# Current_Controller.net
KiCad netlist of a schematic drawn in EAGLE
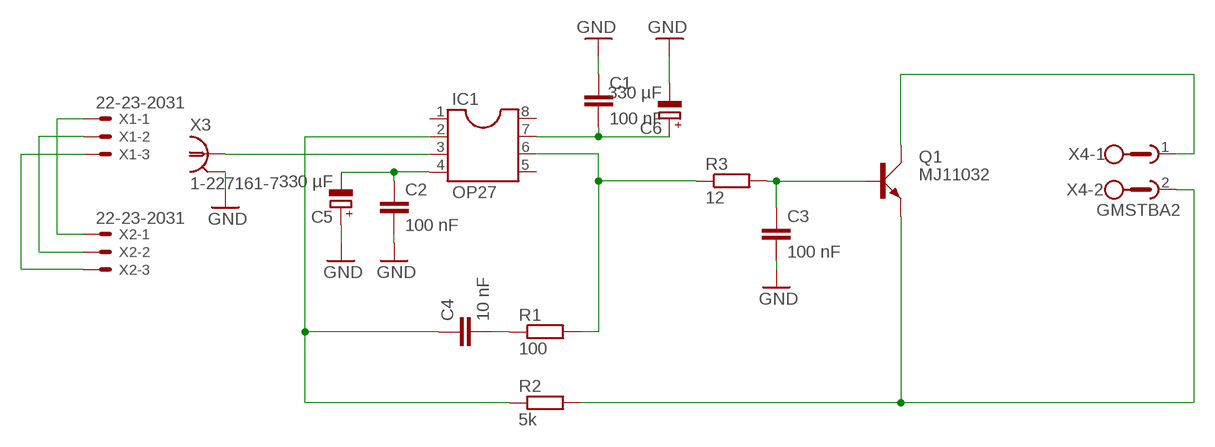
[diagram p0: schematic, sheet 1]

(export (version "E")
  (design (tool "Eeschema 10.0.6"))
  (components
    (comp (ref "C1")
      (value "100 nF")
      (footprint "eagle-import:C025-050X050")
      (libsource (lib "eagle-import") (part "C-EU025-050X050"))
    )
    (comp (ref "C2")
      (value "100 nF")
      (footprint "eagle-import:C025-050X050")
      (libsource (lib "eagle-import") (part "C-EU025-050X050"))
    )
    (comp (ref "C3")
      (value "100 nF")
      (footprint "eagle-import:C025-050X050")
      (libsource (lib "eagle-import") (part "C-EU025-050X050"))
    )
    (comp (ref "C4")
      (value "10 nF")
      (footprint "eagle-import:C025-050X050")
      (libsource (lib "eagle-import") (part "C-EU025-050X050"))
    )
    (comp (ref "C5")
      (value "330 µF")
      (footprint "eagle-import:E5-8,5")
      (libsource (lib "eagle-import") (part "CPOL-EUE5-8.5"))
    )
    (comp (ref "C6")
      (value "330 µF")
      (footprint "eagle-import:E5-8,5")
      (libsource (lib "eagle-import") (part "CPOL-EUE5-8.5"))
    )
    (comp (ref "IC1")
      (value "OP27")
      (footprint "eagle-import:DIL08")
      (libsource (lib "eagle-import") (part "DIL8"))
    )
    (comp (ref "Q1")
      (value "MJ11032")
      (footprint "eagle-import:TO3A")
      (libsource (lib "eagle-import") (part "2N3055"))
    )
    (comp (ref "R1")
      (value "100")
      (footprint "eagle-import:0309_12")
      (libsource (lib "eagle-import") (part "R-EU_0309/12"))
    )
    (comp (ref "R2")
      (value "5k")
      (footprint "eagle-import:0309_12")
      (libsource (lib "eagle-import") (part "R-EU_0309/12"))
    )
    (comp (ref "R3")
      (value "12")
      (footprint "eagle-import:0309_12")
      (libsource (lib "eagle-import") (part "R-EU_0309/12"))
    )
    (comp (ref "X1")
      (value "22-23-2031")
      (footprint "eagle-import:22-23-2031")
      (fields (field (name "MF") "MOLEX"))
      (libsource (lib "eagle-import") (part "22-23-2031"))
    )
    (comp (ref "X2")
      (value "22-23-2031")
      (footprint "eagle-import:22-23-2031")
      (fields (field (name "MF") "MOLEX"))
      (libsource (lib "eagle-import") (part "22-23-2031"))
    )
    (comp (ref "X3")
      (value "1-227161-7")
      (footprint "eagle-import:AMP_227161")
      (fields (field (name "MF") "TYCO ELECTRONICS"))
      (libsource (lib "eagle-import") (part "?2271611--7"))
    )
    (comp (ref "X4")
      (value "GMSTBA2")
      (footprint "eagle-import:GMSTBA2")
      (fields (field (name "MF") "FARNELL") (field (name "MPN") "1757242"))
      (libsource (lib "eagle-import") (part "GMSTBA2"))
    )
  )
  (nets
    (net (code "1") (name "/V+") (class "Default")
      (node (ref "C1") (pin "2") (pinfunction "2_2") (pintype "passive"))
      (node (ref "C6") (pin "+") (pinfunction "+_+") (pintype "passive"))
      (node (ref "IC1") (pin "7") (pinfunction "7_7") (pintype "passive"))
      (node (ref "X1") (pin "1") (pinfunction "S_1") (pintype "passive"))
      (node (ref "X2") (pin "1") (pinfunction "S_1") (pintype "passive"))
    )
    (net (code "2") (name "/V-") (class "Default")
      (node (ref "C2") (pin "1") (pinfunction "1_1") (pintype "passive"))
      (node (ref "C5") (pin "-") (pinfunction "-_-") (pintype "passive"))
      (node (ref "IC1") (pin "4") (pinfunction "4_4") (pintype "passive"))
      (node (ref "X1") (pin "3") (pinfunction "S_3") (pintype "passive"))
      (node (ref "X2") (pin "3") (pinfunction "S_3") (pintype "passive"))
    )
    (net (code "3") (name "GND") (class "Default")
      (node (ref "C1") (pin "1") (pinfunction "1_1") (pintype "passive"))
      (node (ref "C2") (pin "2") (pinfunction "2_2") (pintype "passive"))
      (node (ref "C3") (pin "2") (pinfunction "2_2") (pintype "passive"))
      (node (ref "C5") (pin "+") (pinfunction "+_+") (pintype "passive"))
      (node (ref "C6") (pin "-") (pinfunction "-_-") (pintype "passive"))
      (node (ref "X1") (pin "2") (pinfunction "S_2") (pintype "passive"))
      (node (ref "X2") (pin "2") (pinfunction "S_2") (pintype "passive"))
      (node (ref "X3") (pin "2") (pinfunction "2_2") (pintype "passive"))
    )
    (net (code "4") (name "Net-(C3-Pad1)") (class "Default")
      (node (ref "C3") (pin "1") (pinfunction "1_1") (pintype "passive"))
      (node (ref "Q1") (pin "B") (pinfunction "B_B") (pintype "passive"))
      (node (ref "R3") (pin "2") (pinfunction "2_2") (pintype "passive"))
    )
    (net (code "5") (name "Net-(C4-Pad1)") (class "Default")
      (node (ref "C4") (pin "1") (pinfunction "1_1") (pintype "passive"))
      (node (ref "IC1") (pin "2") (pinfunction "2_2") (pintype "passive"))
      (node (ref "R2") (pin "1") (pinfunction "1_1") (pintype "passive"))
    )
    (net (code "6") (name "Net-(C4-Pad2)") (class "Default")
      (node (ref "C4") (pin "2") (pinfunction "2_2") (pintype "passive"))
      (node (ref "R1") (pin "1") (pinfunction "1_1") (pintype "passive"))
    )
    (net (code "7") (name "Net-(IC1-Pad3)") (class "Default")
      (node (ref "IC1") (pin "3") (pinfunction "3_3") (pintype "passive"))
      (node (ref "X3") (pin "1") (pinfunction "1_1") (pintype "passive"))
    )
    (net (code "8") (name "Net-(IC1-Pad6)") (class "Default")
      (node (ref "IC1") (pin "6") (pinfunction "6_6") (pintype "passive"))
      (node (ref "R1") (pin "2") (pinfunction "2_2") (pintype "passive"))
      (node (ref "R3") (pin "1") (pinfunction "1_1") (pintype "passive"))
    )
    (net (code "9") (name "Net-(Q1-C-PadC1)") (class "Default")
      (node (ref "Q1") (pin "C") (pinfunction "C_C") (pintype "passive"))
      (node (ref "Q1") (pin "C1") (pinfunction "C_C1") (pintype "passive"))
      (node (ref "X4") (pin "1") (pinfunction "1_1") (pintype "passive"))
    )
    (net (code "10") (name "Net-(X4B-1)") (class "Default")
      (node (ref "Q1") (pin "E") (pinfunction "E_E") (pintype "passive"))
      (node (ref "R2") (pin "2") (pinfunction "2_2") (pintype "passive"))
      (node (ref "X4") (pin "2") (pinfunction "1_2") (pintype "passive"))
    )
    (net (code "11") (name "unconnected-(IC1-Pad1)") (class "Default")
      (node (ref "IC1") (pin "1") (pinfunction "1_1") (pintype "passive"))
    )
    (net (code "12") (name "unconnected-(IC1-Pad5)") (class "Default")
      (node (ref "IC1") (pin "5") (pinfunction "5_5") (pintype "passive"))
    )
    (net (code "13") (name "unconnected-(IC1-Pad8)") (class "Default")
      (node (ref "IC1") (pin "8") (pinfunction "8_8") (pintype "passive"))
    )
  )
)
